# ProPrj_Flipper_-_TweenWave_2025-09-01.net
KiCad netlist of a schematic drawn in EasyEDA Pro
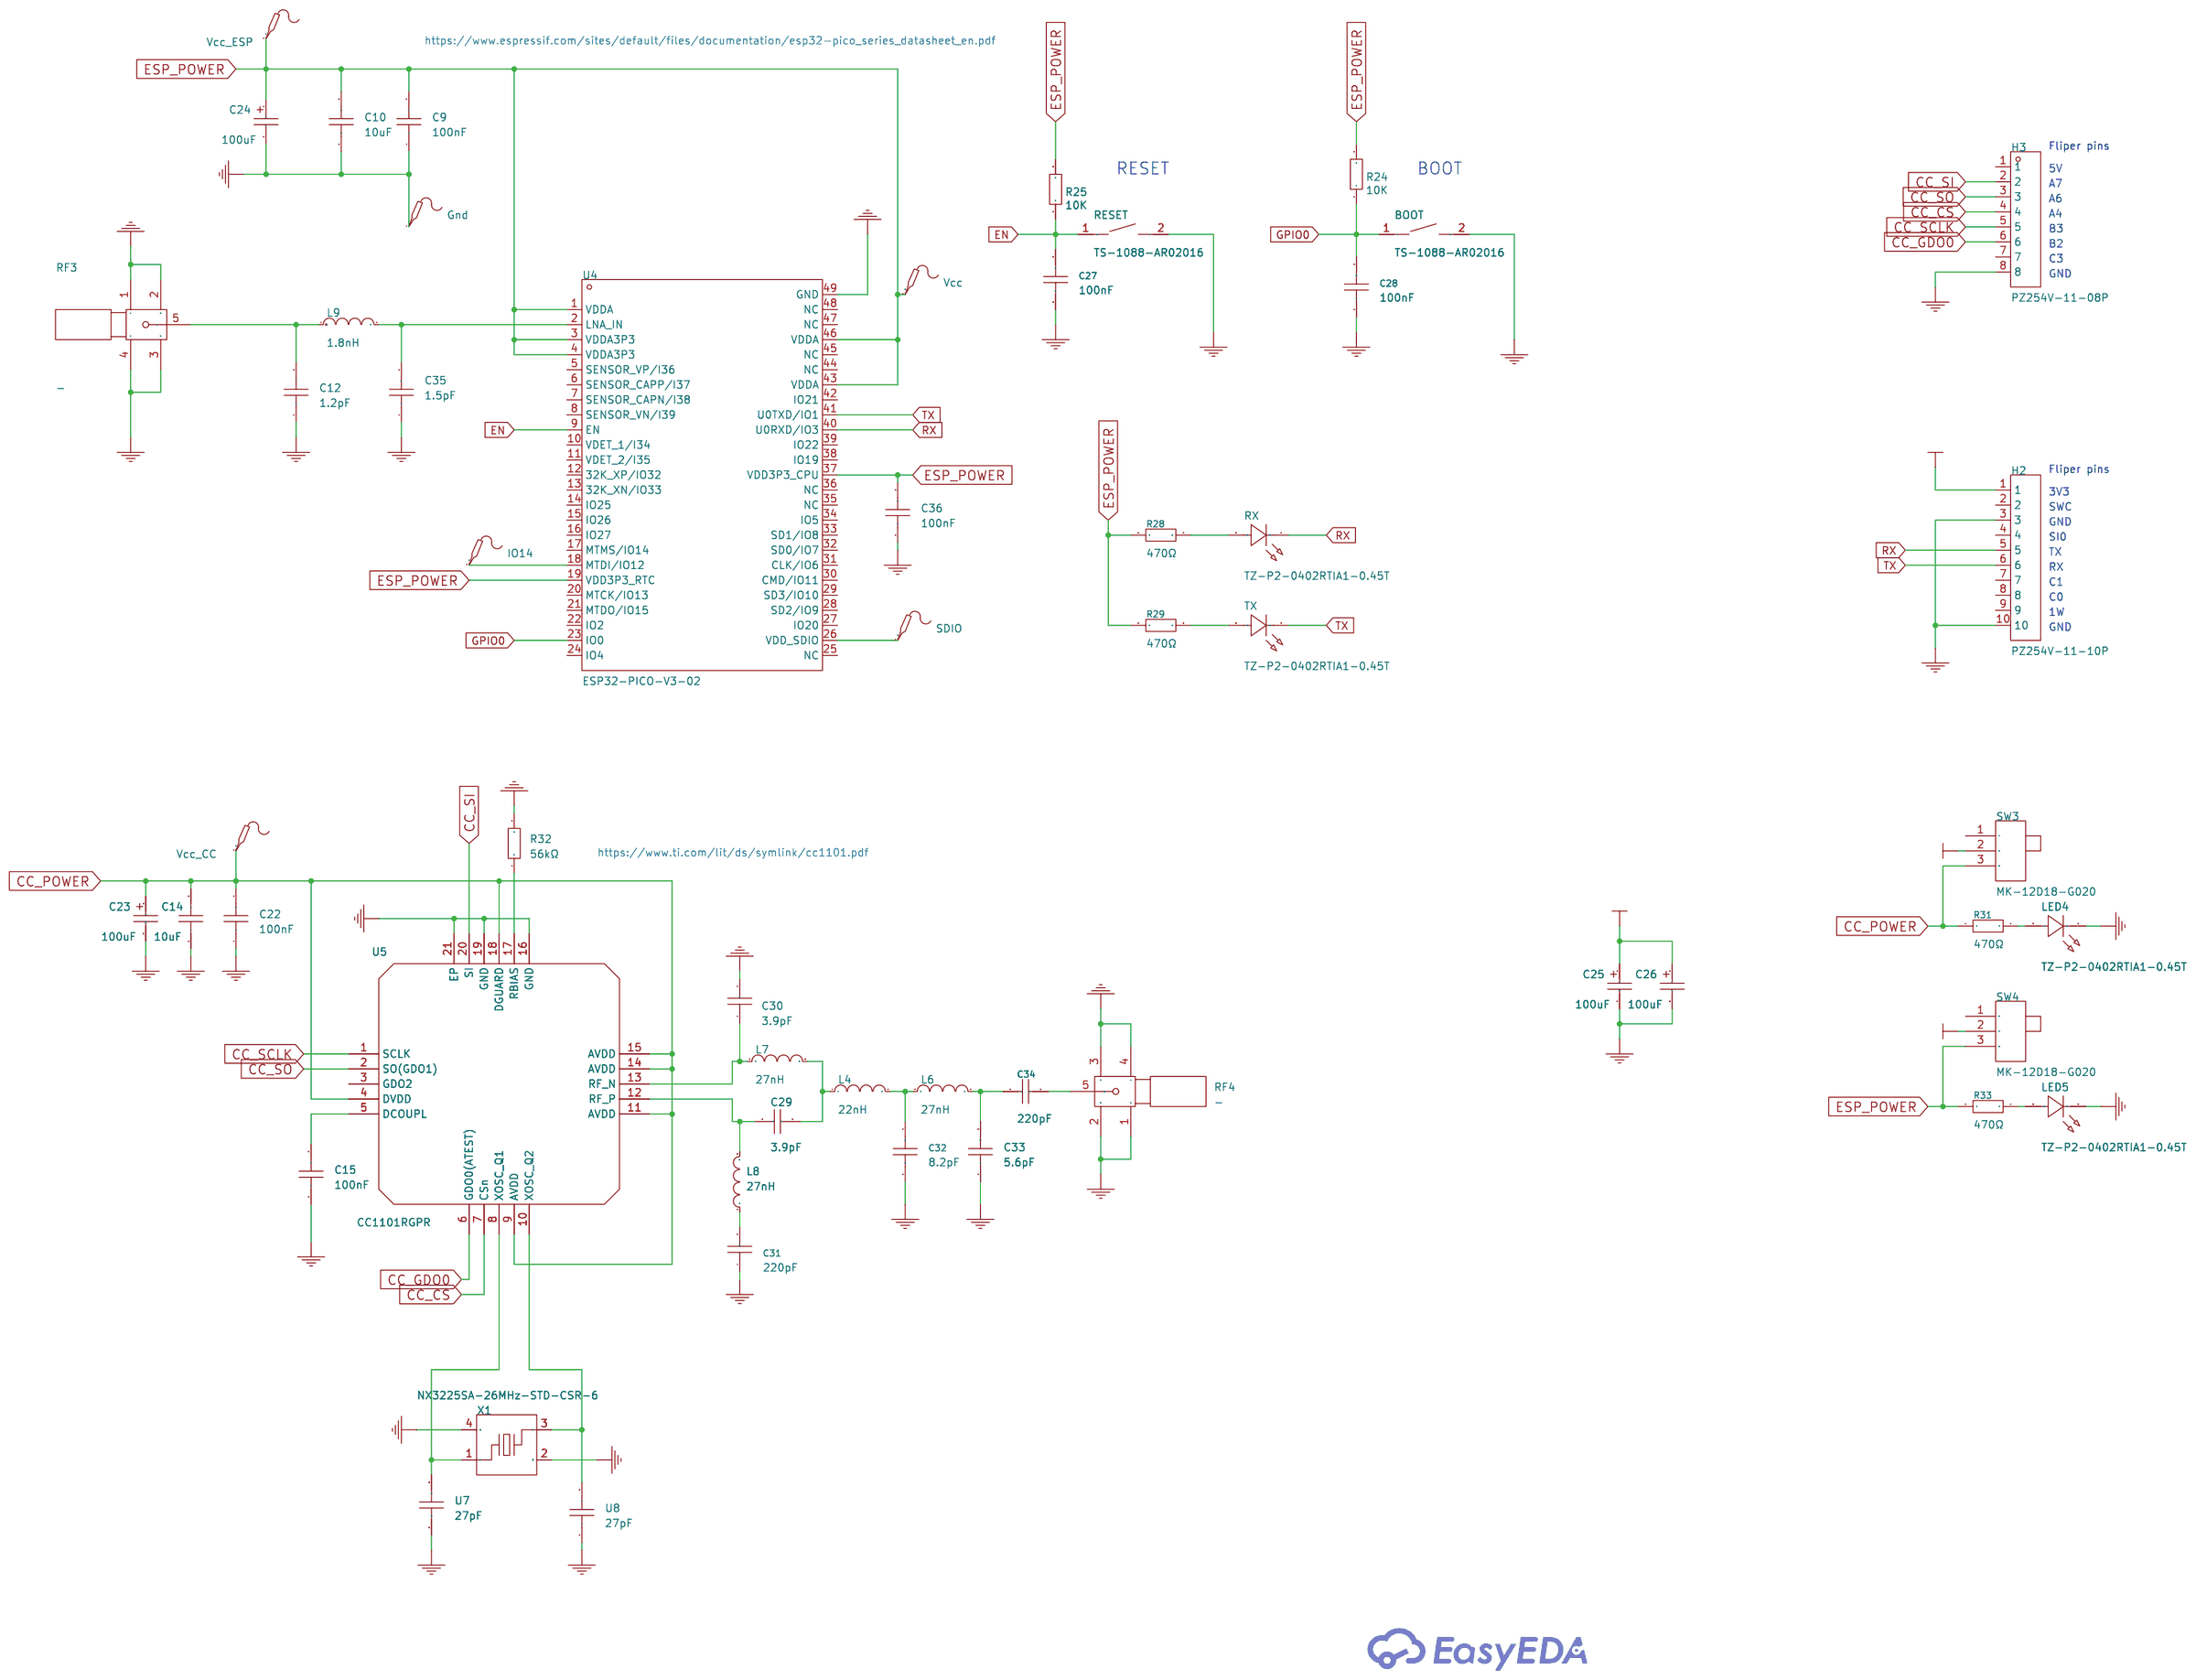
[diagram p0: schematic sheet]

(export (version "E")
  (design (tool "Eeschema 10.0.6"))
  (components
    (comp (ref "BOOT")
      (value "TS-1088-AR02016")
      (footprint "easyedapro:SW-SMD_L3.9-W3.0-P4.45")
      (fields (field (name "Manufacturer") "XUNPU(讯普)"))
      (libsource (lib "easyedapro") (part "TS-1088-AR02016"))
    )
    (comp (ref "C9")
      (value "100nF")
      (footprint "easyedapro:C0603")
      (description "Capacitance:100nF Tolerance:±10% Tolerance:±10% Voltage Rating:50V Temperature Coefficient:X7R")
      (fields
        (field (name "Manufacturer Part") "CC0603KRX7R9BB104")
        (field (name "Manufacturer") "YAGEO(国巨)")
      )
      (libsource (lib "easyedapro") (part "CC0603KRX7R9BB104"))
    )
    (comp (ref "C10")
      (value "10uF")
      (footprint "easyedapro:C0603")
      (fields
        (field (name "Manufacturer Part") "CL10A106MP8NNNC")
        (field (name "Manufacturer") "SAMSUNG(三星)")
      )
      (libsource (lib "easyedapro") (part "CL10A106MP8NNNC"))
    )
    (comp (ref "C12")
      (value "1.2pF")
      (footprint "easyedapro:C0201")
      (fields
        (field (name "Manufacturer Part") "GRM0335C1H1R2BA01D")
        (field (name "Manufacturer") "muRata(村田)")
      )
      (libsource (lib "easyedapro") (part "GRM0335C1H1R2BA01D"))
    )
    (comp (ref "C14")
      (value "10uF")
      (footprint "easyedapro:C0603")
      (fields
        (field (name "Manufacturer Part") "CL10A106MP8NNNC")
        (field (name "Manufacturer") "SAMSUNG(三星)")
      )
      (libsource (lib "easyedapro") (part "CL10A106MP8NNNC"))
    )
    (comp (ref "C15")
      (value "100nF")
      (footprint "easyedapro:C0603")
      (description "Capacitance:100nF Tolerance:±10% Tolerance:±10% Voltage Rating:50V Temperature Coefficient:X7R")
      (fields
        (field (name "Manufacturer Part") "CC0603KRX7R9BB104")
        (field (name "Manufacturer") "YAGEO(国巨)")
      )
      (libsource (lib "easyedapro") (part "CC0603KRX7R9BB104"))
    )
    (comp (ref "C22")
      (value "100nF")
      (footprint "easyedapro:C0603")
      (description "Capacitance:100nF Tolerance:±10% Tolerance:±10% Voltage Rating:50V Temperature Coefficient:X7R")
      (fields
        (field (name "Manufacturer Part") "CC0603KRX7R9BB104")
        (field (name "Manufacturer") "YAGEO(国巨)")
      )
      (libsource (lib "easyedapro") (part "CC0603KRX7R9BB104"))
    )
    (comp (ref "C23")
      (value "100uF")
      (footprint "easyedapro:CASE-B_3528")
      (fields (field (name "Manufacturer Part") "TAJB107K006RNJ") (field (name "Manufacturer") "Kyocera AVX"))
      (libsource (lib "easyedapro") (part "TAJB107K006RNJ"))
    )
    (comp (ref "C24")
      (value "100uF")
      (footprint "easyedapro:CASE-B_3528")
      (fields (field (name "Manufacturer Part") "TAJB107K006RNJ") (field (name "Manufacturer") "Kyocera AVX"))
      (libsource (lib "easyedapro") (part "TAJB107K006RNJ"))
    )
    (comp (ref "C25")
      (value "100uF")
      (footprint "easyedapro:CASE-B_3528")
      (fields (field (name "Manufacturer Part") "TAJB107K006RNJ") (field (name "Manufacturer") "Kyocera AVX"))
      (libsource (lib "easyedapro") (part "TAJB107K006RNJ"))
    )
    (comp (ref "C26")
      (value "100uF")
      (footprint "easyedapro:CASE-B_3528")
      (fields (field (name "Manufacturer Part") "TAJB107K006RNJ") (field (name "Manufacturer") "Kyocera AVX"))
      (libsource (lib "easyedapro") (part "TAJB107K006RNJ"))
    )
    (comp (ref "C27")
      (value "100nF")
      (footprint "easyedapro:C0402")
      (fields
        (field (name "Manufacturer Part") "CC0402KRX7R7BB104")
        (field (name "Manufacturer") "YAGEO(国巨)")
      )
      (libsource (lib "easyedapro") (part "CC0402KRX7R7BB104"))
    )
    (comp (ref "C28")
      (value "100nF")
      (footprint "easyedapro:C0402")
      (fields
        (field (name "Manufacturer Part") "CC0402KRX7R7BB104")
        (field (name "Manufacturer") "YAGEO(国巨)")
      )
      (libsource (lib "easyedapro") (part "CC0402KRX7R7BB104"))
    )
    (comp (ref "C29")
      (value "3.9pF")
      (footprint "easyedapro:C0402")
      (fields (field (name "Manufacturer Part") "0402CG3R9C500NT") (field (name "Manufacturer") "FH(风华)"))
      (libsource (lib "easyedapro") (part "0402CG3R9C500NT"))
    )
    (comp (ref "C30")
      (value "3.9pF")
      (footprint "easyedapro:C0402")
      (fields (field (name "Manufacturer Part") "0402CG3R9C500NT") (field (name "Manufacturer") "FH(风华)"))
      (libsource (lib "easyedapro") (part "0402CG3R9C500NT"))
    )
    (comp (ref "C31")
      (value "220pF")
      (footprint "easyedapro:C0402")
      (description "Capacitance:220pF Tolerance:±5% Tolerance:±5% Voltage Rating:50V Temperature Coefficient:NP0")
      (fields
        (field (name "Manufacturer Part") "CC0402JRNPO9BN221")
        (field (name "Manufacturer") "YAGEO(国巨)")
      )
      (libsource (lib "easyedapro") (part "CC0402JRNPO9BN221"))
    )
    (comp (ref "C32")
      (value "8.2pF")
      (footprint "easyedapro:C0402")
      (fields
        (field (name "Manufacturer Part") "CC0402BRNPO9BN8R2")
        (field (name "Manufacturer") "YAGEO(国巨)")
      )
      (libsource (lib "easyedapro") (part "CC0402BRNPO9BN8R2"))
    )
    (comp (ref "C33")
      (value "5.6pF")
      (footprint "easyedapro:C0402")
      (fields
        (field (name "Manufacturer Part") "CC0402BRNPO9BN5R6")
        (field (name "Manufacturer") "YAGEO(国巨)")
      )
      (libsource (lib "easyedapro") (part "CC0402BRNPO9BN5R6"))
    )
    (comp (ref "C34")
      (value "220pF")
      (footprint "easyedapro:C0402")
      (description "Capacitance:220pF Tolerance:±5% Tolerance:±5% Voltage Rating:50V Temperature Coefficient:NP0")
      (fields
        (field (name "Manufacturer Part") "CC0402JRNPO9BN221")
        (field (name "Manufacturer") "YAGEO(国巨)")
      )
      (libsource (lib "easyedapro") (part "CC0402JRNPO9BN221"))
    )
    (comp (ref "C35")
      (value "1.5pF")
      (footprint "easyedapro:C0201")
      (fields
        (field (name "Manufacturer Part") "GRM0335C1H1R5BA01D")
        (field (name "Manufacturer") "muRata(村田)")
      )
      (libsource (lib "easyedapro") (part "GRM0335C1H1R5BA01D"))
    )
    (comp (ref "C36")
      (value "100nF")
      (footprint "easyedapro:C0603")
      (description "Capacitance:100nF Tolerance:±10% Tolerance:±10% Voltage Rating:50V Temperature Coefficient:X7R")
      (fields
        (field (name "Manufacturer Part") "CC0603KRX7R9BB104")
        (field (name "Manufacturer") "YAGEO(国巨)")
      )
      (libsource (lib "easyedapro") (part "CC0603KRX7R9BB104"))
    )
    (comp (ref "Gnd")
      (value "~")
      (footprint "easyedapro:Test-Point-0.5mm")
      (description "Test Point 测试点")
      (libsource (lib "easyedapro") (part "Test-Point"))
    )
    (comp (ref "H2")
      (value "PZ254V-11-10P")
      (footprint "easyedapro:HDR-TH_10P-P2.54-V-M")
      (fields (field (name "Manufacturer") "XFCN(兴飞)"))
      (libsource (lib "easyedapro") (part "PZ254V-11-10P"))
    )
    (comp (ref "H3")
      (value "PZ254V-11-08P")
      (footprint "easyedapro:HDR-TH_8P-P2.54-V-M")
      (fields (field (name "Manufacturer") "XFCN(兴飞)"))
      (libsource (lib "easyedapro") (part "PZ254V-11-08P"))
    )
    (comp (ref "IO14")
      (value "~")
      (footprint "easyedapro:Test-Point-0.5mm")
      (description "Test Point 测试点")
      (libsource (lib "easyedapro") (part "Test-Point"))
    )
    (comp (ref "L4")
      (value "22nH")
      (footprint "easyedapro:L0402")
      (fields (field (name "Manufacturer Part") "LQG15HS22NJ02D") (field (name "Manufacturer") "muRata(村田)"))
      (libsource (lib "easyedapro") (part "LQG15HS22NJ02D"))
    )
    (comp (ref "L6")
      (value "27nH")
      (footprint "easyedapro:L0402-RD")
      (fields (field (name "Manufacturer Part") "LQG15HS27NJ02D") (field (name "Manufacturer") "muRata(村田)"))
      (libsource (lib "easyedapro") (part "LQG15HS27NJ02D"))
    )
    (comp (ref "L7")
      (value "27nH")
      (footprint "easyedapro:L0402-RD")
      (fields (field (name "Manufacturer Part") "LQG15HS27NJ02D") (field (name "Manufacturer") "muRata(村田)"))
      (libsource (lib "easyedapro") (part "LQG15HS27NJ02D"))
    )
    (comp (ref "L8")
      (value "27nH")
      (footprint "easyedapro:L0402-RD")
      (fields (field (name "Manufacturer Part") "LQG15HS27NJ02D") (field (name "Manufacturer") "muRata(村田)"))
      (libsource (lib "easyedapro") (part "LQG15HS27NJ02D"))
    )
    (comp (ref "L9")
      (value "1.8nH")
      (footprint "easyedapro:L0201-RD")
      (fields (field (name "Manufacturer Part") "LQP03TN1N8B02D") (field (name "Manufacturer") "muRata(村田)"))
      (libsource (lib "easyedapro") (part "LQP03TN1N8B02D"))
    )
    (comp (ref "LED4")
      (value "TZ-P2-0402RTIA1-0.45T")
      (footprint "easyedapro:LED0402-RD_RED")
      (fields (field (name "Manufacturer") "TUOZHAN(拓展光电)"))
      (libsource (lib "easyedapro") (part "TZ-P2-0402RTIA1-0.45T"))
    )
    (comp (ref "LED5")
      (value "TZ-P2-0402RTIA1-0.45T")
      (footprint "easyedapro:LED0402-RD_RED")
      (fields (field (name "Manufacturer") "TUOZHAN(拓展光电)"))
      (libsource (lib "easyedapro") (part "TZ-P2-0402RTIA1-0.45T"))
    )
    (comp (ref "R24")
      (value "10K")
      (footprint "easyedapro:R0603")
      (fields (field (name "Manufacturer Part") "RC0603DR-0710KL") (field (name "Manufacturer") "YAGEO(国巨)"))
      (libsource (lib "easyedapro") (part "10K"))
    )
    (comp (ref "R25")
      (value "10K")
      (footprint "easyedapro:R0603")
      (fields (field (name "Manufacturer Part") "RC0603DR-0710KL") (field (name "Manufacturer") "YAGEO(国巨)"))
      (libsource (lib "easyedapro") (part "10K"))
    )
    (comp (ref "R28")
      (value "470Ω")
      (footprint "easyedapro:R0402")
      (fields
        (field (name "Manufacturer Part") "0402WGF4700TCE")
        (field (name "Manufacturer") "UNI-ROYAL(厚声)")
      )
      (libsource (lib "easyedapro") (part "0402WGF4700TCE"))
    )
    (comp (ref "R29")
      (value "470Ω")
      (footprint "easyedapro:R0402")
      (fields
        (field (name "Manufacturer Part") "0402WGF4700TCE")
        (field (name "Manufacturer") "UNI-ROYAL(厚声)")
      )
      (libsource (lib "easyedapro") (part "0402WGF4700TCE"))
    )
    (comp (ref "R31")
      (value "470Ω")
      (footprint "easyedapro:R0402")
      (fields
        (field (name "Manufacturer Part") "0402WGF4700TCE")
        (field (name "Manufacturer") "UNI-ROYAL(厚声)")
      )
      (libsource (lib "easyedapro") (part "0402WGF4700TCE"))
    )
    (comp (ref "R32")
      (value "56kΩ")
      (footprint "easyedapro:R0402")
      (fields
        (field (name "Manufacturer Part") "0402WGF5602TCE")
        (field (name "Manufacturer") "UNI-ROYAL(厚声)")
      )
      (libsource (lib "easyedapro") (part "0402WGF5602TCE"))
    )
    (comp (ref "R33")
      (value "470Ω")
      (footprint "easyedapro:R0402")
      (fields
        (field (name "Manufacturer Part") "0402WGF4700TCE")
        (field (name "Manufacturer") "UNI-ROYAL(厚声)")
      )
      (libsource (lib "easyedapro") (part "0402WGF4700TCE"))
    )
    (comp (ref "RESET")
      (value "TS-1088-AR02016")
      (footprint "easyedapro:SW-SMD_L3.9-W3.0-P4.45")
      (fields (field (name "Manufacturer") "XUNPU(讯普)"))
      (libsource (lib "easyedapro") (part "TS-1088-AR02016"))
    )
    (comp (ref "RF3")
      (value "-")
      (footprint "easyedapro:SMA-SMD_BWSMA-KE-P001")
      (fields
        (field (name "Manufacturer Part") "BWSMA-KE-P001")
        (field (name "Manufacturer") "BAT WIRELESS(蝙蝠无线)")
      )
      (libsource (lib "easyedapro") (part "BWSMA-KE-P001"))
    )
    (comp (ref "RF4")
      (value "-")
      (footprint "easyedapro:SMA-SMD_BWSMA-KE-P001")
      (fields
        (field (name "Manufacturer Part") "BWSMA-KE-P001")
        (field (name "Manufacturer") "BAT WIRELESS(蝙蝠无线)")
      )
      (libsource (lib "easyedapro") (part "BWSMA-KE-P001"))
    )
    (comp (ref "RX")
      (value "TZ-P2-0402RTIA1-0.45T")
      (footprint "easyedapro:LED0402-RD_RED")
      (fields (field (name "Manufacturer") "TUOZHAN(拓展光电)"))
      (libsource (lib "easyedapro") (part "TZ-P2-0402RTIA1-0.45T"))
    )
    (comp (ref "SDIO")
      (value "~")
      (footprint "easyedapro:Test-Point-0.5mm")
      (description "Test Point 测试点")
      (libsource (lib "easyedapro") (part "Test-Point"))
    )
    (comp (ref "SW3")
      (value "MK-12D18-G020")
      (footprint "easyedapro:SW-TH_MK-12D18-G040")
      (fields (field (name "Manufacturer") "G-Switch(品赞)"))
      (libsource (lib "easyedapro") (part "MK-12D18-G020"))
    )
    (comp (ref "SW4")
      (value "MK-12D18-G020")
      (footprint "easyedapro:SW-TH_MK-12D18-G040")
      (fields (field (name "Manufacturer") "G-Switch(品赞)"))
      (libsource (lib "easyedapro") (part "MK-12D18-G020"))
    )
    (comp (ref "TX")
      (value "TZ-P2-0402RTIA1-0.45T")
      (footprint "easyedapro:LED0402-RD_RED")
      (fields (field (name "Manufacturer") "TUOZHAN(拓展光电)"))
      (libsource (lib "easyedapro") (part "TZ-P2-0402RTIA1-0.45T"))
    )
    (comp (ref "U4")
      (value "ESP32-PICO-V3-02")
      (footprint "easyedapro:QFN-48_L7.0-W7.0-P0.50-BL-EP5.1")
      (fields (field (name "Manufacturer") "ESPRESSIF(乐鑫)"))
      (libsource (lib "easyedapro") (part "ESP32-PICO-V3-02"))
    )
    (comp (ref "U5")
      (value "CC1101RGPR")
      (footprint "easyedapro:QFN-20_L4.0-W4.0-P0.5-TL-EP")
      (fields (field (name "Manufacturer") "TI(德州仪器)"))
      (libsource (lib "easyedapro") (part "CC1101RGPR"))
    )
    (comp (ref "U7")
      (value "27pF")
      (footprint "easyedapro:C0402")
      (description "Capacitance: Tolerance:±1% Tolerance:±1% Voltage Rated:50V")
      (fields
        (field (name "Manufacturer Part") "GCM1555C1H270FA16D")
        (field (name "Manufacturer") "muRata(村田)")
      )
      (libsource (lib "easyedapro") (part "GCM1555C1H270FA16D"))
    )
    (comp (ref "U8")
      (value "27pF")
      (footprint "easyedapro:C0402")
      (description "Capacitance: Tolerance:±1% Tolerance:±1% Voltage Rated:50V")
      (fields
        (field (name "Manufacturer Part") "GCM1555C1H270FA16D")
        (field (name "Manufacturer") "muRata(村田)")
      )
      (libsource (lib "easyedapro") (part "GCM1555C1H270FA16D"))
    )
    (comp (ref "Vcc")
      (value "~")
      (footprint "easyedapro:Test-Point-0.5mm")
      (description "Test Point 测试点")
      (libsource (lib "easyedapro") (part "Test-Point"))
    )
    (comp (ref "Vcc_CC")
      (value "~")
      (footprint "easyedapro:Test-Point-0.5mm")
      (description "Test Point 测试点")
      (libsource (lib "easyedapro") (part "Test-Point"))
    )
    (comp (ref "Vcc_ESP")
      (value "~")
      (footprint "easyedapro:Test-Point-0.5mm")
      (description "Test Point 测试点")
      (libsource (lib "easyedapro") (part "Test-Point"))
    )
    (comp (ref "X1")
      (value "NX3225SA-26MHz-STD-CSR-6")
      (footprint "easyedapro:CRYSTAL-SMD_4P-L3.2-W2.5-BL")
      (fields (field (name "Manufacturer") "NDK"))
      (libsource (lib "easyedapro") (part "NX3225SA-26MHZ-STD-CSR-6"))
    )
  )
  (nets
    (net (code "1") (name "3V3") (class "Default")
      (node (ref "C25") (pin "1") (pinfunction "1_1") (pintype "input"))
      (node (ref "C26") (pin "1") (pinfunction "1_1") (pintype "input"))
      (node (ref "H2") (pin "1") (pinfunction "1_1") (pintype "unspecified"))
      (node (ref "SW3") (pin "2") (pinfunction "2_2") (pintype "unspecified"))
      (node (ref "SW4") (pin "2") (pinfunction "2_2") (pintype "unspecified"))
    )
    (net (code "2") (name "CC_CS") (class "Default")
      (node (ref "H3") (pin "4") (pinfunction "4_4") (pintype "unspecified"))
      (node (ref "U5") (pin "7") (pinfunction "CSn_7") (pintype "unspecified"))
    )
    (net (code "3") (name "CC_GDO0") (class "Default")
      (node (ref "H3") (pin "6") (pinfunction "6_6") (pintype "unspecified"))
      (node (ref "U5") (pin "6") (pinfunction "GDO0(ATEST)_6") (pintype "unspecified"))
    )
    (net (code "4") (name "CC_POWER") (class "Default")
      (node (ref "C14") (pin "2") (pinfunction "2_2") (pintype "unspecified"))
      (node (ref "C22") (pin "2") (pinfunction "2_2") (pintype "unspecified"))
      (node (ref "C23") (pin "1") (pinfunction "1_1") (pintype "input"))
      (node (ref "R31") (pin "1") (pinfunction "1_1") (pintype "input"))
      (node (ref "SW3") (pin "3") (pinfunction "3_3") (pintype "unspecified"))
      (node (ref "U5") (pin "11") (pinfunction "AVDD_11") (pintype "unspecified"))
      (node (ref "U5") (pin "14") (pinfunction "AVDD_14") (pintype "unspecified"))
      (node (ref "U5") (pin "15") (pinfunction "AVDD_15") (pintype "unspecified"))
      (node (ref "U5") (pin "18") (pinfunction "DGUARD_18") (pintype "unspecified"))
      (node (ref "U5") (pin "4") (pinfunction "DVDD_4") (pintype "unspecified"))
      (node (ref "U5") (pin "9") (pinfunction "AVDD_9") (pintype "unspecified"))
      (node (ref "Vcc_CC") (pin "1") (pinfunction "1_1") (pintype "unspecified"))
    )
    (net (code "5") (name "CC_SCLK") (class "Default")
      (node (ref "H3") (pin "5") (pinfunction "5_5") (pintype "unspecified"))
      (node (ref "U5") (pin "1") (pinfunction "SCLK_1") (pintype "unspecified"))
    )
    (net (code "6") (name "CC_SI") (class "Default")
      (node (ref "H3") (pin "2") (pinfunction "2_2") (pintype "unspecified"))
      (node (ref "U5") (pin "20") (pinfunction "SI_20") (pintype "unspecified"))
    )
    (net (code "7") (name "CC_SO") (class "Default")
      (node (ref "H3") (pin "3") (pinfunction "3_3") (pintype "unspecified"))
      (node (ref "U5") (pin "2") (pinfunction "SO(GDO1)_2") (pintype "unspecified"))
    )
    (net (code "8") (name "EN") (class "Default")
      (node (ref "C27") (pin "2") (pinfunction "2_2") (pintype "input"))
      (node (ref "R25") (pin "1") (pinfunction "1_1") (pintype "input"))
      (node (ref "RESET") (pin "1") (pinfunction "1_1") (pintype "unspecified"))
      (node (ref "U4") (pin "9") (pinfunction "EN_9") (pintype "unspecified"))
    )
    (net (code "9") (name "ESP_POWER") (class "Default")
      (node (ref "C10") (pin "2") (pinfunction "2_2") (pintype "unspecified"))
      (node (ref "C24") (pin "1") (pinfunction "1_1") (pintype "input"))
      (node (ref "C36") (pin "2") (pinfunction "2_2") (pintype "unspecified"))
      (node (ref "C9") (pin "2") (pinfunction "2_2") (pintype "unspecified"))
      (node (ref "R24") (pin "2") (pinfunction "2_2") (pintype "input"))
      (node (ref "R25") (pin "2") (pinfunction "2_2") (pintype "input"))
      (node (ref "R28") (pin "1") (pinfunction "1_1") (pintype "input"))
      (node (ref "R29") (pin "1") (pinfunction "1_1") (pintype "input"))
      (node (ref "R33") (pin "1") (pinfunction "1_1") (pintype "input"))
      (node (ref "SW4") (pin "3") (pinfunction "3_3") (pintype "unspecified"))
      (node (ref "U4") (pin "1") (pinfunction "VDDA_1") (pintype "unspecified"))
      (node (ref "U4") (pin "19") (pinfunction "VDD3P3_RTC_19") (pintype "unspecified"))
      (node (ref "U4") (pin "3") (pinfunction "VDDA3P3_3") (pintype "unspecified"))
      (node (ref "U4") (pin "37") (pinfunction "VDD3P3_CPU_37") (pintype "unspecified"))
      (node (ref "U4") (pin "4") (pinfunction "VDDA3P3_4") (pintype "unspecified"))
      (node (ref "U4") (pin "43") (pinfunction "VDDA_43") (pintype "unspecified"))
      (node (ref "U4") (pin "46") (pinfunction "VDDA_46") (pintype "unspecified"))
      (node (ref "Vcc") (pin "1") (pinfunction "1_1") (pintype "unspecified"))
      (node (ref "Vcc_ESP") (pin "1") (pinfunction "1_1") (pintype "unspecified"))
    )
    (net (code "10") (name "GND") (class "Default")
      (node (ref "BOOT") (pin "2") (pinfunction "2_2") (pintype "unspecified"))
      (node (ref "C10") (pin "1") (pinfunction "1_1") (pintype "unspecified"))
      (node (ref "C12") (pin "1") (pinfunction "1_1") (pintype "unspecified"))
      (node (ref "C14") (pin "1") (pinfunction "1_1") (pintype "unspecified"))
      (node (ref "C15") (pin "1") (pinfunction "1_1") (pintype "unspecified"))
      (node (ref "C22") (pin "1") (pinfunction "1_1") (pintype "unspecified"))
      (node (ref "C23") (pin "2") (pinfunction "2_2") (pintype "input"))
      (node (ref "C24") (pin "2") (pinfunction "2_2") (pintype "input"))
      (node (ref "C25") (pin "2") (pinfunction "2_2") (pintype "input"))
      (node (ref "C26") (pin "2") (pinfunction "2_2") (pintype "input"))
      (node (ref "C27") (pin "1") (pinfunction "1_1") (pintype "input"))
      (node (ref "C28") (pin "1") (pinfunction "1_1") (pintype "input"))
      (node (ref "C30") (pin "2") (pinfunction "2_2") (pintype "input"))
      (node (ref "C31") (pin "1") (pinfunction "1_1") (pintype "input"))
      (node (ref "C32") (pin "2") (pinfunction "2_2") (pintype "input"))
      (node (ref "C33") (pin "1") (pinfunction "1_1") (pintype "unspecified"))
      (node (ref "C35") (pin "1") (pinfunction "1_1") (pintype "unspecified"))
      (node (ref "C36") (pin "1") (pinfunction "1_1") (pintype "unspecified"))
      (node (ref "C9") (pin "1") (pinfunction "1_1") (pintype "unspecified"))
      (node (ref "Gnd") (pin "1") (pinfunction "1_1") (pintype "unspecified"))
      (node (ref "H2") (pin "10") (pinfunction "10_10") (pintype "unspecified"))
      (node (ref "H2") (pin "3") (pinfunction "3_3") (pintype "unspecified"))
      (node (ref "H3") (pin "8") (pinfunction "8_8") (pintype "unspecified"))
      (node (ref "LED4") (pin "1") (pinfunction "K_1") (pintype "unspecified"))
      (node (ref "LED5") (pin "1") (pinfunction "K_1") (pintype "unspecified"))
      (node (ref "R32") (pin "2") (pinfunction "2_2") (pintype "input"))
      (node (ref "RESET") (pin "2") (pinfunction "2_2") (pintype "unspecified"))
      (node (ref "RF3") (pin "1") (pinfunction "1_1") (pintype "unspecified"))
      (node (ref "RF3") (pin "2") (pinfunction "2_2") (pintype "unspecified"))
      (node (ref "RF3") (pin "3") (pinfunction "3_3") (pintype "unspecified"))
      (node (ref "RF3") (pin "4") (pinfunction "4_4") (pintype "unspecified"))
      (node (ref "RF4") (pin "1") (pinfunction "1_1") (pintype "unspecified"))
      (node (ref "RF4") (pin "2") (pinfunction "2_2") (pintype "unspecified"))
      (node (ref "RF4") (pin "3") (pinfunction "3_3") (pintype "unspecified"))
      (node (ref "RF4") (pin "4") (pinfunction "4_4") (pintype "unspecified"))
      (node (ref "U4") (pin "49") (pinfunction "GND_49") (pintype "unspecified"))
      (node (ref "U5") (pin "16") (pinfunction "GND_16") (pintype "unspecified"))
      (node (ref "U5") (pin "19") (pinfunction "GND_19") (pintype "unspecified"))
      (node (ref "U5") (pin "21") (pinfunction "EP_21") (pintype "unspecified"))
      (node (ref "U7") (pin "1") (pinfunction "1_1") (pintype "unspecified"))
      (node (ref "U8") (pin "1") (pinfunction "1_1") (pintype "unspecified"))
      (node (ref "X1") (pin "2") (pinfunction "GND_2") (pintype "input"))
      (node (ref "X1") (pin "4") (pinfunction "GND_4") (pintype "input"))
    )
    (net (code "11") (name "GPIO0") (class "Default")
      (node (ref "BOOT") (pin "1") (pinfunction "1_1") (pintype "unspecified"))
      (node (ref "C28") (pin "2") (pinfunction "2_2") (pintype "input"))
      (node (ref "R24") (pin "1") (pinfunction "1_1") (pintype "input"))
      (node (ref "U4") (pin "23") (pinfunction "IO0_23") (pintype "unspecified"))
    )
    (net (code "12") (name "Net-(C12-Pad2)") (class "Default")
      (node (ref "C12") (pin "2") (pinfunction "2_2") (pintype "unspecified"))
      (node (ref "L9") (pin "1") (pinfunction "1_1") (pintype "input"))
      (node (ref "RF3") (pin "5") (pinfunction "5_5") (pintype "unspecified"))
    )
    (net (code "13") (name "Net-(C29-Pad2)") (class "Default")
      (node (ref "C29") (pin "2") (pinfunction "2_2") (pintype "input"))
      (node (ref "L4") (pin "1") (pinfunction "1_1") (pintype "unspecified"))
      (node (ref "L7") (pin "2") (pinfunction "2_2") (pintype "unspecified"))
    )
    (net (code "14") (name "Net-(C31-Pad2)") (class "Default")
      (node (ref "C31") (pin "2") (pinfunction "2_2") (pintype "input"))
      (node (ref "L8") (pin "1") (pinfunction "1_1") (pintype "unspecified"))
    )
    (net (code "15") (name "Net-(C32-Pad1)") (class "Default")
      (node (ref "C32") (pin "1") (pinfunction "1_1") (pintype "input"))
      (node (ref "L4") (pin "2") (pinfunction "2_2") (pintype "unspecified"))
      (node (ref "L6") (pin "1") (pinfunction "1_1") (pintype "unspecified"))
    )
    (net (code "16") (name "Net-(C33-Pad2)") (class "Default")
      (node (ref "C33") (pin "2") (pinfunction "2_2") (pintype "unspecified"))
      (node (ref "C34") (pin "2") (pinfunction "2_2") (pintype "input"))
      (node (ref "L6") (pin "2") (pinfunction "2_2") (pintype "unspecified"))
    )
    (net (code "17") (name "Net-(C34-Pad1)") (class "Default")
      (node (ref "C34") (pin "1") (pinfunction "1_1") (pintype "input"))
      (node (ref "RF4") (pin "5") (pinfunction "5_5") (pintype "unspecified"))
    )
    (net (code "18") (name "Net-(LED4-A)") (class "Default")
      (node (ref "LED4") (pin "2") (pinfunction "A_2") (pintype "unspecified"))
      (node (ref "R31") (pin "2") (pinfunction "2_2") (pintype "input"))
    )
    (net (code "19") (name "Net-(LED5-A)") (class "Default")
      (node (ref "LED5") (pin "2") (pinfunction "A_2") (pintype "unspecified"))
      (node (ref "R33") (pin "2") (pinfunction "2_2") (pintype "input"))
    )
    (net (code "20") (name "Net-(RX-A)") (class "Default")
      (node (ref "R28") (pin "2") (pinfunction "2_2") (pintype "input"))
      (node (ref "RX") (pin "2") (pinfunction "A_2") (pintype "unspecified"))
    )
    (net (code "21") (name "Net-(TX-A)") (class "Default")
      (node (ref "R29") (pin "2") (pinfunction "2_2") (pintype "input"))
      (node (ref "TX") (pin "2") (pinfunction "A_2") (pintype "unspecified"))
    )
    (net (code "22") (name "Net-(U4-LNA_IN)") (class "Default")
      (node (ref "C35") (pin "2") (pinfunction "2_2") (pintype "unspecified"))
      (node (ref "L9") (pin "2") (pinfunction "2_2") (pintype "input"))
      (node (ref "U4") (pin "2") (pinfunction "LNA_IN_2") (pintype "unspecified"))
    )
    (net (code "23") (name "Net-(U4-MTDI{slash}IO12)") (class "Default")
      (node (ref "IO14") (pin "1") (pinfunction "1_1") (pintype "unspecified"))
      (node (ref "U4") (pin "18") (pinfunction "MTDI/IO12_18") (pintype "unspecified"))
    )
    (net (code "24") (name "Net-(U4-VDD_SDIO)") (class "Default")
      (node (ref "SDIO") (pin "1") (pinfunction "1_1") (pintype "unspecified"))
      (node (ref "U4") (pin "26") (pinfunction "VDD_SDIO_26") (pintype "unspecified"))
    )
    (net (code "25") (name "Net-(U5-DCOUPL)") (class "Default")
      (node (ref "C15") (pin "2") (pinfunction "2_2") (pintype "unspecified"))
      (node (ref "U5") (pin "5") (pinfunction "DCOUPL_5") (pintype "unspecified"))
    )
    (net (code "26") (name "Net-(U5-RBIAS)") (class "Default")
      (node (ref "R32") (pin "1") (pinfunction "1_1") (pintype "input"))
      (node (ref "U5") (pin "17") (pinfunction "RBIAS_17") (pintype "unspecified"))
    )
    (net (code "27") (name "Net-(U5-RF_N)") (class "Default")
      (node (ref "C30") (pin "1") (pinfunction "1_1") (pintype "input"))
      (node (ref "L7") (pin "1") (pinfunction "1_1") (pintype "unspecified"))
      (node (ref "U5") (pin "13") (pinfunction "RF_N_13") (pintype "unspecified"))
    )
    (net (code "28") (name "Net-(U5-RF_P)") (class "Default")
      (node (ref "C29") (pin "1") (pinfunction "1_1") (pintype "input"))
      (node (ref "L8") (pin "2") (pinfunction "2_2") (pintype "unspecified"))
      (node (ref "U5") (pin "12") (pinfunction "RF_P_12") (pintype "unspecified"))
    )
    (net (code "29") (name "Net-(U5-XOSC_Q1)") (class "Default")
      (node (ref "U5") (pin "8") (pinfunction "XOSC_Q1_8") (pintype "unspecified"))
      (node (ref "U7") (pin "2") (pinfunction "2_2") (pintype "unspecified"))
      (node (ref "X1") (pin "1") (pinfunction "1_1") (pintype "input"))
    )
    (net (code "30") (name "Net-(U5-XOSC_Q2)") (class "Default")
      (node (ref "U5") (pin "10") (pinfunction "XOSC_Q2_10") (pintype "unspecified"))
      (node (ref "U8") (pin "2") (pinfunction "2_2") (pintype "unspecified"))
      (node (ref "X1") (pin "3") (pinfunction "3_3") (pintype "input"))
    )
    (net (code "31") (name "RX") (class "Default")
      (node (ref "H2") (pin "5") (pinfunction "5_5") (pintype "unspecified"))
      (node (ref "RX") (pin "1") (pinfunction "K_1") (pintype "unspecified"))
      (node (ref "U4") (pin "40") (pinfunction "U0RXD/IO3_40") (pintype "unspecified"))
    )
    (net (code "32") (name "TX") (class "Default")
      (node (ref "H2") (pin "6") (pinfunction "6_6") (pintype "unspecified"))
      (node (ref "TX") (pin "1") (pinfunction "K_1") (pintype "unspecified"))
      (node (ref "U4") (pin "41") (pinfunction "U0TXD/IO1_41") (pintype "unspecified"))
    )
    (net (code "33") (name "unconnected-(H2-Pad2)") (class "Default")
      (node (ref "H2") (pin "2") (pinfunction "2_2") (pintype "unspecified"))
    )
    (net (code "34") (name "unconnected-(H2-Pad4)") (class "Default")
      (node (ref "H2") (pin "4") (pinfunction "4_4") (pintype "unspecified"))
    )
    (net (code "35") (name "unconnected-(H2-Pad7)") (class "Default")
      (node (ref "H2") (pin "7") (pinfunction "7_7") (pintype "unspecified"))
    )
    (net (code "36") (name "unconnected-(H2-Pad8)") (class "Default")
      (node (ref "H2") (pin "8") (pinfunction "8_8") (pintype "unspecified"))
    )
    (net (code "37") (name "unconnected-(H2-Pad9)") (class "Default")
      (node (ref "H2") (pin "9") (pinfunction "9_9") (pintype "unspecified"))
    )
    (net (code "38") (name "unconnected-(H3-Pad1)") (class "Default")
      (node (ref "H3") (pin "1") (pinfunction "1_1") (pintype "unspecified"))
    )
    (net (code "39") (name "unconnected-(H3-Pad7)") (class "Default")
      (node (ref "H3") (pin "7") (pinfunction "7_7") (pintype "unspecified"))
    )
    (net (code "40") (name "unconnected-(SW3-Pad1)") (class "Default")
      (node (ref "SW3") (pin "1") (pinfunction "1_1") (pintype "unspecified"))
    )
    (net (code "41") (name "unconnected-(SW4-Pad1)") (class "Default")
      (node (ref "SW4") (pin "1") (pinfunction "1_1") (pintype "unspecified"))
    )
    (net (code "42") (name "unconnected-(U4-32K_XN{slash}IO33-Pad13)") (class "Default")
      (node (ref "U4") (pin "13") (pinfunction "32K_XN/IO33_13") (pintype "unspecified"))
    )
    (net (code "43") (name "unconnected-(U4-32K_XP{slash}IO32-Pad12)") (class "Default")
      (node (ref "U4") (pin "12") (pinfunction "32K_XP/IO32_12") (pintype "unspecified"))
    )
    (net (code "44") (name "unconnected-(U4-CLK{slash}IO6-Pad31)") (class "Default")
      (node (ref "U4") (pin "31") (pinfunction "CLK/IO6_31") (pintype "unspecified"))
    )
    (net (code "45") (name "unconnected-(U4-CMD{slash}IO11-Pad30)") (class "Default")
      (node (ref "U4") (pin "30") (pinfunction "CMD/IO11_30") (pintype "unspecified"))
    )
    (net (code "46") (name "unconnected-(U4-IO2-Pad22)") (class "Default")
      (node (ref "U4") (pin "22") (pinfunction "IO2_22") (pintype "unspecified"))
    )
    (net (code "47") (name "unconnected-(U4-IO4-Pad24)") (class "Default")
      (node (ref "U4") (pin "24") (pinfunction "IO4_24") (pintype "unspecified"))
    )
    (net (code "48") (name "unconnected-(U4-IO5-Pad34)") (class "Default")
      (node (ref "U4") (pin "34") (pinfunction "IO5_34") (pintype "unspecified"))
    )
    (net (code "49") (name "unconnected-(U4-IO19-Pad38)") (class "Default")
      (node (ref "U4") (pin "38") (pinfunction "IO19_38") (pintype "unspecified"))
    )
    (net (code "50") (name "unconnected-(U4-IO20-Pad27)") (class "Default")
      (node (ref "U4") (pin "27") (pinfunction "IO20_27") (pintype "unspecified"))
    )
    (net (code "51") (name "unconnected-(U4-IO21-Pad42)") (class "Default")
      (node (ref "U4") (pin "42") (pinfunction "IO21_42") (pintype "unspecified"))
    )
    (net (code "52") (name "unconnected-(U4-IO22-Pad39)") (class "Default")
      (node (ref "U4") (pin "39") (pinfunction "IO22_39") (pintype "unspecified"))
    )
    (net (code "53") (name "unconnected-(U4-IO25-Pad14)") (class "Default")
      (node (ref "U4") (pin "14") (pinfunction "IO25_14") (pintype "unspecified"))
    )
    (net (code "54") (name "unconnected-(U4-IO26-Pad15)") (class "Default")
      (node (ref "U4") (pin "15") (pinfunction "IO26_15") (pintype "unspecified"))
    )
    (net (code "55") (name "unconnected-(U4-IO27-Pad16)") (class "Default")
      (node (ref "U4") (pin "16") (pinfunction "IO27_16") (pintype "unspecified"))
    )
    (net (code "56") (name "unconnected-(U4-MTCK{slash}IO13-Pad20)") (class "Default")
      (node (ref "U4") (pin "20") (pinfunction "MTCK/IO13_20") (pintype "unspecified"))
    )
    (net (code "57") (name "unconnected-(U4-MTDO{slash}IO15-Pad21)") (class "Default")
      (node (ref "U4") (pin "21") (pinfunction "MTDO/IO15_21") (pintype "unspecified"))
    )
    (net (code "58") (name "unconnected-(U4-MTMS{slash}IO14-Pad17)") (class "Default")
      (node (ref "U4") (pin "17") (pinfunction "MTMS/IO14_17") (pintype "unspecified"))
    )
    (net (code "59") (name "unconnected-(U4-NC-Pad25)") (class "Default")
      (node (ref "U4") (pin "25") (pinfunction "NC_25") (pintype "unspecified"))
    )
    (net (code "60") (name "unconnected-(U4-NC-Pad35)") (class "Default")
      (node (ref "U4") (pin "35") (pinfunction "NC_35") (pintype "unspecified"))
    )
    (net (code "61") (name "unconnected-(U4-NC-Pad36)") (class "Default")
      (node (ref "U4") (pin "36") (pinfunction "NC_36") (pintype "unspecified"))
    )
    (net (code "62") (name "unconnected-(U4-NC-Pad44)") (class "Default")
      (node (ref "U4") (pin "44") (pinfunction "NC_44") (pintype "unspecified"))
    )
    (net (code "63") (name "unconnected-(U4-NC-Pad45)") (class "Default")
      (node (ref "U4") (pin "45") (pinfunction "NC_45") (pintype "unspecified"))
    )
    (net (code "64") (name "unconnected-(U4-NC-Pad47)") (class "Default")
      (node (ref "U4") (pin "47") (pinfunction "NC_47") (pintype "unspecified"))
    )
    (net (code "65") (name "unconnected-(U4-NC-Pad48)") (class "Default")
      (node (ref "U4") (pin "48") (pinfunction "NC_48") (pintype "unspecified"))
    )
    (net (code "66") (name "unconnected-(U4-SD0{slash}IO7-Pad32)") (class "Default")
      (node (ref "U4") (pin "32") (pinfunction "SD0/IO7_32") (pintype "unspecified"))
    )
    (net (code "67") (name "unconnected-(U4-SD1{slash}IO8-Pad33)") (class "Default")
      (node (ref "U4") (pin "33") (pinfunction "SD1/IO8_33") (pintype "unspecified"))
    )
    (net (code "68") (name "unconnected-(U4-SD2{slash}IO9-Pad28)") (class "Default")
      (node (ref "U4") (pin "28") (pinfunction "SD2/IO9_28") (pintype "unspecified"))
    )
    (net (code "69") (name "unconnected-(U4-SD3{slash}IO10-Pad29)") (class "Default")
      (node (ref "U4") (pin "29") (pinfunction "SD3/IO10_29") (pintype "unspecified"))
    )
    (net (code "70") (name "unconnected-(U4-SENSOR_CAPN{slash}I38-Pad7)") (class "Default")
      (node (ref "U4") (pin "7") (pinfunction "SENSOR_CAPN/I38_7") (pintype "unspecified"))
    )
    (net (code "71") (name "unconnected-(U4-SENSOR_CAPP{slash}I37-Pad6)") (class "Default")
      (node (ref "U4") (pin "6") (pinfunction "SENSOR_CAPP/I37_6") (pintype "unspecified"))
    )
    (net (code "72") (name "unconnected-(U4-SENSOR_VN{slash}I39-Pad8)") (class "Default")
      (node (ref "U4") (pin "8") (pinfunction "SENSOR_VN/I39_8") (pintype "unspecified"))
    )
    (net (code "73") (name "unconnected-(U4-SENSOR_VP{slash}I36-Pad5)") (class "Default")
      (node (ref "U4") (pin "5") (pinfunction "SENSOR_VP/I36_5") (pintype "unspecified"))
    )
    (net (code "74") (name "unconnected-(U4-VDET_1{slash}I34-Pad10)") (class "Default")
      (node (ref "U4") (pin "10") (pinfunction "VDET_1/I34_10") (pintype "unspecified"))
    )
    (net (code "75") (name "unconnected-(U4-VDET_2{slash}I35-Pad11)") (class "Default")
      (node (ref "U4") (pin "11") (pinfunction "VDET_2/I35_11") (pintype "unspecified"))
    )
    (net (code "76") (name "unconnected-(U5-GDO2-Pad3)") (class "Default")
      (node (ref "U5") (pin "3") (pinfunction "GDO2_3") (pintype "unspecified"))
    )
  )
)
